# Overo_Carrier.net
KiCad netlist of a schematic drawn in Altium Designer
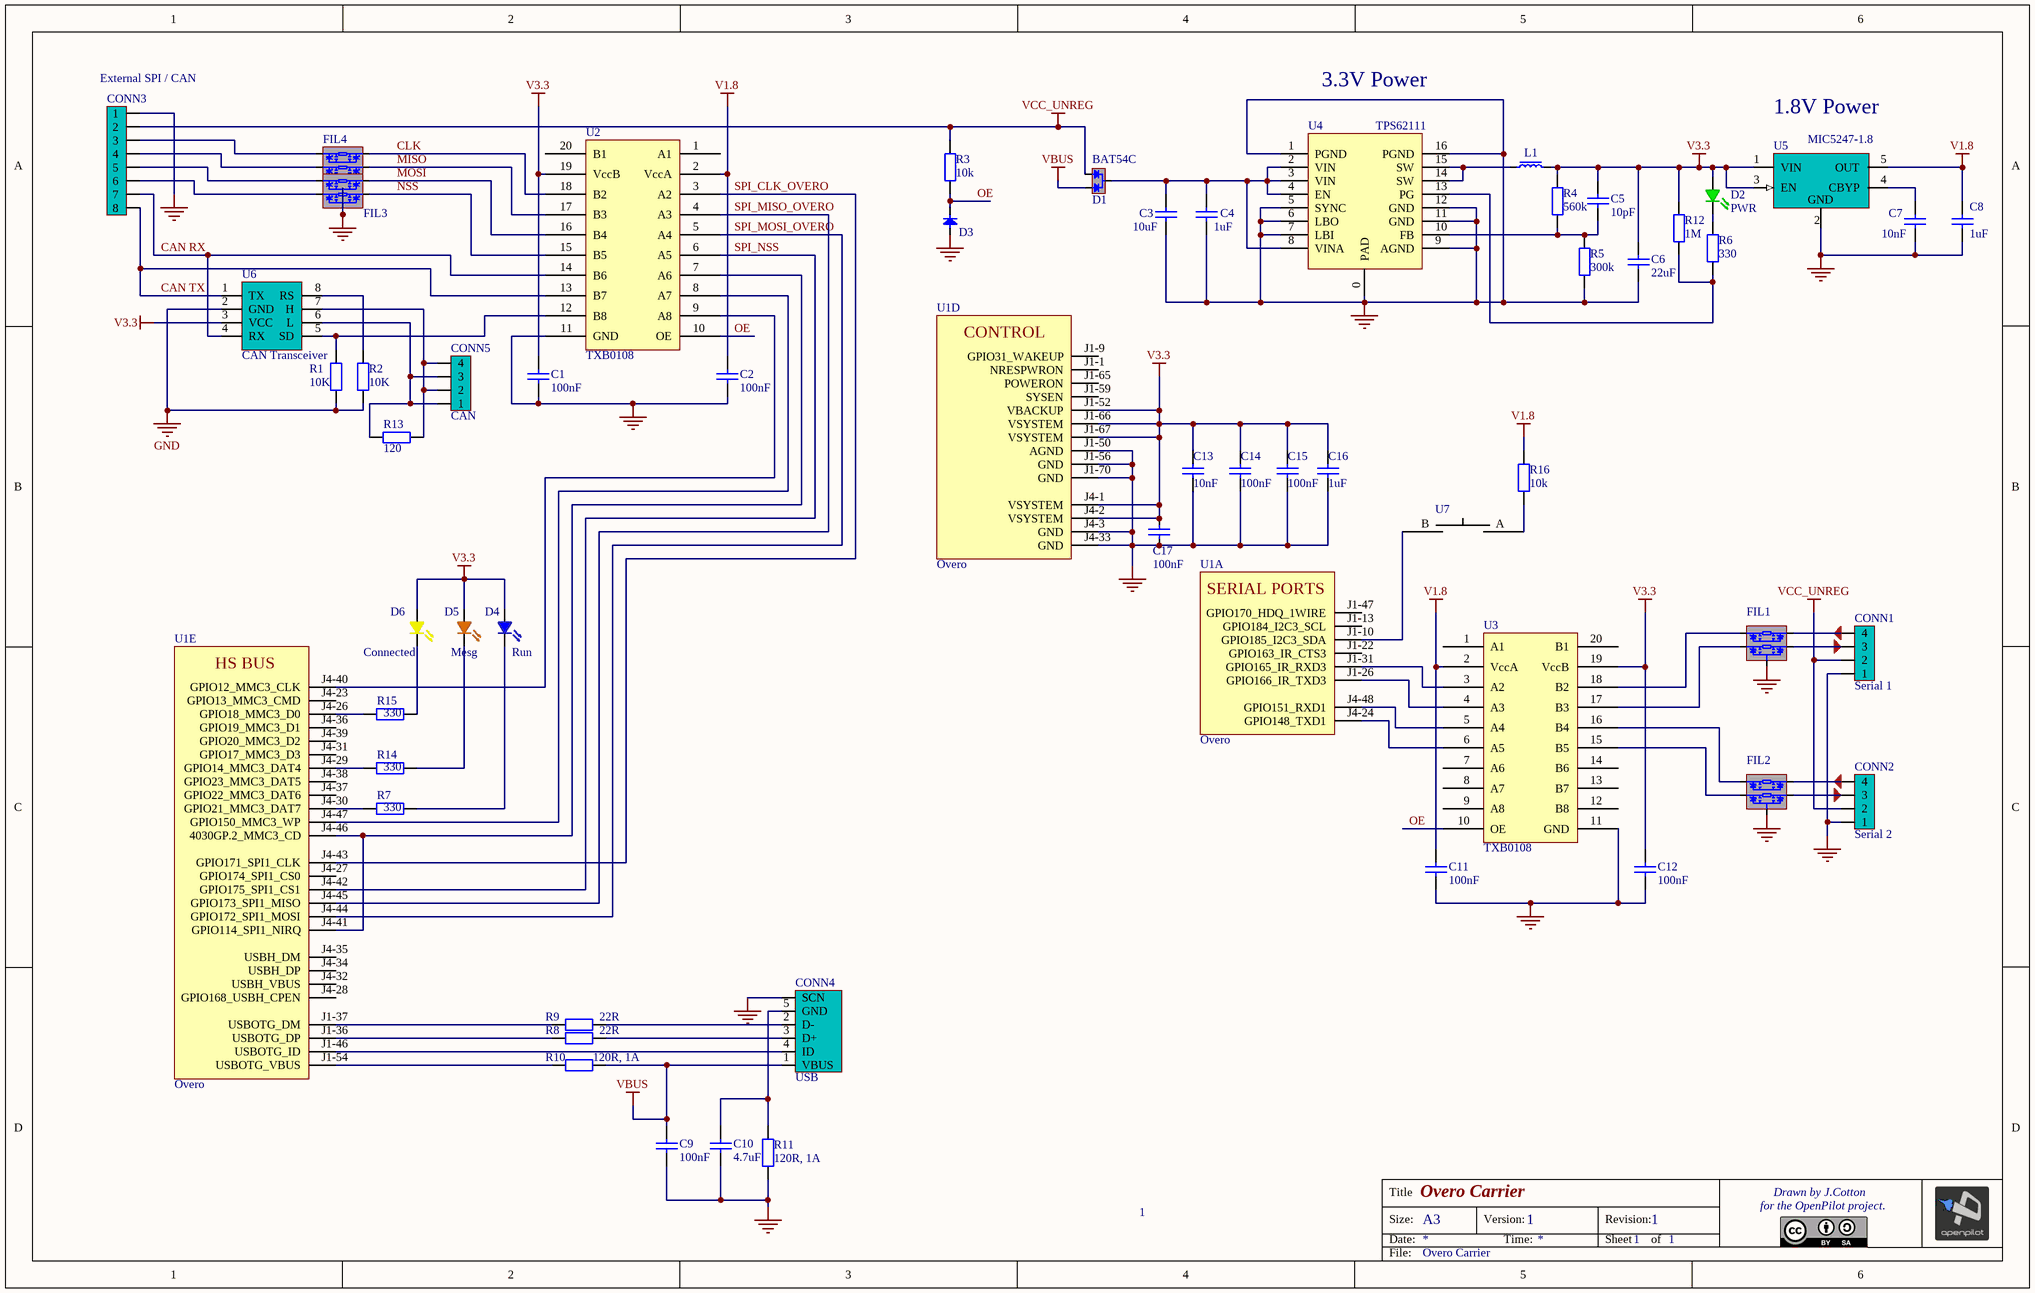
[diagram p0: Overo Carrier.SchDoc]

(export (version "E")
  (design (tool "Eeschema 10.0.6"))
  (components
    (comp (ref "C1")
      (value "100nF")
      (footprint "CAP603N")
      (description "Capacitor SMD")
      (fields (field (name "Comment") "Cap603") (field (name "PUBLISHER") "The OpenPilot Project"))
      (libsource (lib "OpenPilot") (part "Cap603"))
    )
    (comp (ref "C2")
      (value "100nF")
      (footprint "CAP603N")
      (description "Capacitor SMD")
      (fields (field (name "Comment") "Cap603") (field (name "PUBLISHER") "The OpenPilot Project"))
      (libsource (lib "OpenPilot") (part "Cap603"))
    )
    (comp (ref "C3")
      (value "10uF")
      (footprint "CAP805N")
      (description "Capacitor SMD")
      (fields (field (name "Comment") "Cap805") (field (name "PUBLISHER") "The OpenPilot Project"))
      (libsource (lib "OpenPilot") (part "Cap805"))
    )
    (comp (ref "C4")
      (value "1uF")
      (footprint "CAP603L")
      (description "Capacitor SMD")
      (fields (field (name "Comment") "Cap603") (field (name "PUBLISHER") "The OpenPilot Project"))
      (libsource (lib "OpenPilot") (part "Cap603"))
    )
    (comp (ref "C5")
      (value "10pF")
      (footprint "CAP603N")
      (description "Capacitor SMD")
      (fields (field (name "Comment") "Cap603") (field (name "PUBLISHER") "The OpenPilot Project"))
      (libsource (lib "OpenPilot") (part "Cap603"))
    )
    (comp (ref "C6")
      (value "22uF")
      (footprint "CAP805N")
      (description "Capacitor SMD")
      (fields (field (name "Comment") "Cap805") (field (name "PUBLISHER") "The OpenPilot Project"))
      (libsource (lib "OpenPilot") (part "Cap805"))
    )
    (comp (ref "C7")
      (value "10nF")
      (footprint "CAP603N")
      (description "Capacitor SMD")
      (fields (field (name "Comment") "Cap603") (field (name "PUBLISHER") "The OpenPilot Project"))
      (libsource (lib "OpenPilot") (part "Cap603"))
    )
    (comp (ref "C8")
      (value "1uF")
      (footprint "CAP603L")
      (description "Capacitor SMD")
      (fields (field (name "Comment") "Cap603") (field (name "PUBLISHER") "The OpenPilot Project"))
      (libsource (lib "OpenPilot") (part "Cap603"))
    )
    (comp (ref "C9")
      (value "100nF")
      (footprint "CAP603N")
      (description "Capacitor SMD")
      (fields (field (name "Comment") "Cap603") (field (name "PUBLISHER") "The OpenPilot Project"))
      (libsource (lib "OpenPilot") (part "Cap603"))
    )
    (comp (ref "C10")
      (value "4.7uF")
      (footprint "CAP603L")
      (description "Capacitor SMD")
      (fields (field (name "Comment") "Cap603") (field (name "PUBLISHER") "The OpenPilot Project"))
      (libsource (lib "OpenPilot") (part "Cap603"))
    )
    (comp (ref "C11")
      (value "100nF")
      (footprint "CAP603N")
      (description "Capacitor SMD")
      (fields (field (name "Comment") "Cap603") (field (name "PUBLISHER") "The OpenPilot Project"))
      (libsource (lib "OpenPilot") (part "Cap603"))
    )
    (comp (ref "C12")
      (value "100nF")
      (footprint "CAP603N")
      (description "Capacitor SMD")
      (fields (field (name "Comment") "Cap603") (field (name "PUBLISHER") "The OpenPilot Project"))
      (libsource (lib "OpenPilot") (part "Cap603"))
    )
    (comp (ref "C13")
      (value "10nF")
      (footprint "CAP603N")
      (description "Capacitor SMD")
      (fields (field (name "Comment") "Cap603") (field (name "PUBLISHER") "The OpenPilot Project"))
      (libsource (lib "OpenPilot") (part "Cap603"))
    )
    (comp (ref "C14")
      (value "100nF")
      (footprint "CAP603N")
      (description "Capacitor SMD")
      (fields (field (name "Comment") "Cap603") (field (name "PUBLISHER") "The OpenPilot Project"))
      (libsource (lib "OpenPilot") (part "Cap603"))
    )
    (comp (ref "C15")
      (value "100nF")
      (footprint "CAP603N")
      (description "Capacitor SMD")
      (fields (field (name "Comment") "Cap603") (field (name "PUBLISHER") "The OpenPilot Project"))
      (libsource (lib "OpenPilot") (part "Cap603"))
    )
    (comp (ref "C16")
      (value "1uF")
      (footprint "CAP603L")
      (description "Capacitor SMD")
      (fields (field (name "Comment") "Cap603") (field (name "PUBLISHER") "The OpenPilot Project"))
      (libsource (lib "OpenPilot") (part "Cap603"))
    )
    (comp (ref "C17")
      (value "100nF")
      (footprint "CAP603N")
      (description "Capacitor SMD")
      (fields (field (name "Comment") "Cap603") (field (name "PUBLISHER") "The OpenPilot Project"))
      (libsource (lib "") (part "Cap603_1"))
    )
    (comp (ref "CONN1")
      (value "Serial 1")
      (footprint "JST SH 4 Pin Side Entry")
      (description "JST-SH 4-pin Side Entry Socket")
      (fields (field (name "MANUFACTURER") "Generic Components"))
      (libsource (lib "OpenPilot") (part "JST-SH 4-pin Side Entry Socket"))
    )
    (comp (ref "CONN2")
      (value "Serial 2")
      (footprint "JST SH 4 Pin Side Entry")
      (description "JST-SH 4-pin Side Entry Socket")
      (fields (field (name "MANUFACTURER") "Generic Components"))
      (libsource (lib "OpenPilot") (part "JST-SH 4-pin Side Entry Socket"))
    )
    (comp (ref "CONN3")
      (value "External SPI / CAN")
      (footprint "JST SH 8 Pin Side Entry")
      (description "JST-SH 8-pin Side Entry Socket")
      (fields
        (field (name "MANUFACTURER") "Generic Components")
        (field (name "PUBLISHER") "The OpenPilot Project")
      )
      (libsource (lib "OpenPilot") (part "JST-SH 8-pin Side Entry Socket"))
    )
    (comp (ref "CONN4")
      (value "USB")
      (footprint "USB SMD")
      (description "USB Type-B SMT Socket")
      (libsource (lib "OpenPilot") (part "USB_SMT_B"))
    )
    (comp (ref "CONN5")
      (value "CAN")
      (footprint "JST SH 4 Pin Side Entry")
      (description "JST-SH 4-pin Side Entry Socket")
      (fields (field (name "MANUFACTURER") "Generic Components"))
      (libsource (lib "OpenPilot") (part "JST-SH 4-pin Side Entry Socket"))
    )
    (comp (ref "D1")
      (value "BAT54C")
      (footprint "SOT23-3N")
      (description "Dual Diode Command Cathode")
      (fields
        (field (name "MANUFACTURER") "STMicroelectronics")
        (field (name "MANUFACTURER PART NUMBER") "BAT54CFILM")
      )
      (libsource (lib "OpenPilot") (part "BAT54C"))
    )
    (comp (ref "D2")
      (value "PWR")
      (footprint "LED603N")
      (description "Green 603 LED")
      (libsource (lib "OpenPilot") (part "LED 603 Gr"))
    )
    (comp (ref "D3")
      (value "Diode Zen 3.3V 0603")
      (footprint "IND603N")
      (description "Diode Zener 3.3V 150MW 0603")
      (libsource (lib "OpenPilot") (part "Diode Zener 3.3V 150MW 0603"))
    )
    (comp (ref "D4")
      (value "Run")
      (footprint "LED603N")
      (description "Blue 603 LED")
      (libsource (lib "OpenPilot") (part "LED 603 Bl"))
    )
    (comp (ref "D5")
      (value "Mesg")
      (footprint "LED603N")
      (description "Orange 603 LED")
      (fields (field (name "PUBLISHER") "The OpenPilot Project"))
      (libsource (lib "OpenPilot") (part "LED 603 Or"))
    )
    (comp (ref "D6")
      (value "Connected")
      (footprint "LED603N")
      (description "Yellow 603 LED")
      (fields (field (name "PUBLISHER") "The OpenPilot Project"))
      (libsource (lib "OpenPilot") (part "LED 603 Yellow"))
    )
    (comp (ref "FIL1")
      (value "IP4256CZ5-W,115")
      (footprint "SOT-665")
      (description "IP4256CZ5-W,115 2 channel, 100R, 30pF, RF ESD Filter")
      (fields
        (field (name "MANUFACTURER") "Generic Components")
        (field (name "PUBLISHER") "The OpenPilot Project")
      )
      (libsource (lib "OpenPilot") (part "RF Filter 100R 30pF"))
    )
    (comp (ref "FIL2")
      (value "IP4256CZ5-W,115")
      (footprint "SOT-665")
      (description "IP4256CZ5-W,115 2 channel, 100R, 30pF, RF ESD Filter")
      (fields
        (field (name "MANUFACTURER") "Generic Components")
        (field (name "PUBLISHER") "The OpenPilot Project")
      )
      (libsource (lib "OpenPilot") (part "RF Filter 100R 30pF"))
    )
    (comp (ref "FIL3")
      (value "IP4256CZ5-W,115")
      (footprint "SOT-665")
      (description "IP4256CZ5-W,115 2 channel, 100R, 30pF, RF ESD Filter")
      (fields
        (field (name "MANUFACTURER") "Generic Components")
        (field (name "PUBLISHER") "The OpenPilot Project")
      )
      (libsource (lib "") (part "RF Filter 100R 30pF_1"))
    )
    (comp (ref "FIL4")
      (value "IP4256CZ5-W,115")
      (footprint "SOT-665")
      (description "IP4256CZ5-W,115 2 channel, 100R, 30pF, RF ESD Filter")
      (fields
        (field (name "MANUFACTURER") "Generic Components")
        (field (name "PUBLISHER") "The OpenPilot Project")
      )
      (libsource (lib "") (part "RF Filter 100R 30pF_1"))
    )
    (comp (ref "L1")
      (value "FB 550mA 6.8µH 0805")
      (footprint "IND805L")
      (description "Ferrite Bead 550mA 6.8µH")
      (fields
        (field (name "MANUFACTURER") "Generic Components")
        (field (name "PUBLISHER") "The OpenPilot Project")
      )
      (libsource (lib "OpenPilot") (part "Ferrite Bead 550mA 6.8µH 0805"))
    )
    (comp (ref "R1")
      (value "10K")
      (footprint "RES603N")
      (description "Resistor SMD")
      (fields (field (name "Comment") "Res603") (field (name "PUBLISHER") "The OpenPilot Project"))
      (libsource (lib "OpenPilot") (part "Res603"))
    )
    (comp (ref "R2")
      (value "10K")
      (footprint "RES603N")
      (description "Resistor SMD")
      (fields (field (name "Comment") "Res603") (field (name "PUBLISHER") "The OpenPilot Project"))
      (libsource (lib "OpenPilot") (part "Res603"))
    )
    (comp (ref "R3")
      (value "10k")
      (footprint "RES603N")
      (description "Resistor SMD")
      (fields (field (name "Comment") "Res603") (field (name "PUBLISHER") "The OpenPilot Project"))
      (libsource (lib "") (part "Res603_1"))
    )
    (comp (ref "R4")
      (value "560k")
      (footprint "RES603N")
      (description "Resistor SMD")
      (fields (field (name "Comment") "Res603") (field (name "PUBLISHER") "The OpenPilot Project"))
      (libsource (lib "OpenPilot") (part "Res603"))
    )
    (comp (ref "R5")
      (value "300k")
      (footprint "RES603N")
      (description "Resistor SMD")
      (fields (field (name "Comment") "Res603") (field (name "PUBLISHER") "The OpenPilot Project"))
      (libsource (lib "OpenPilot") (part "Res603"))
    )
    (comp (ref "R6")
      (value "330")
      (footprint "RES603N")
      (description "Resistor SMD")
      (fields (field (name "Comment") "Res603") (field (name "PUBLISHER") "The OpenPilot Project"))
      (libsource (lib "OpenPilot") (part "Res603"))
    )
    (comp (ref "R7")
      (value "330")
      (footprint "RES603N")
      (description "Resistor SMD")
      (fields (field (name "Comment") "Res603") (field (name "PUBLISHER") "The OpenPilot Project"))
      (libsource (lib "") (part "Res603_3"))
    )
    (comp (ref "R8")
      (value "22R")
      (footprint "RES603N")
      (description "Resistor SMD")
      (fields (field (name "Comment") "Res603") (field (name "PUBLISHER") "The OpenPilot Project"))
      (libsource (lib "") (part "Res603_2"))
    )
    (comp (ref "R9")
      (value "22R")
      (footprint "RES603N")
      (description "Resistor SMD")
      (fields (field (name "Comment") "Res603") (field (name "PUBLISHER") "The OpenPilot Project"))
      (libsource (lib "") (part "Res603_2"))
    )
    (comp (ref "R10")
      (value "120R, 1A")
      (footprint "RES805L")
      (description "Resistor SMD")
      (fields (field (name "Comment") "Res805") (field (name "PUBLISHER") "The OpenPilot Project"))
      (libsource (lib "OpenPilot") (part "Res805"))
    )
    (comp (ref "R11")
      (value "120R, 1A")
      (footprint "RES805L")
      (description "Resistor SMD")
      (fields (field (name "Comment") "Res805") (field (name "PUBLISHER") "The OpenPilot Project"))
      (libsource (lib "") (part "Res805_1"))
    )
    (comp (ref "R12")
      (value "1M")
      (footprint "RES603N")
      (description "Resistor SMD")
      (fields (field (name "Comment") "Res603") (field (name "PUBLISHER") "The OpenPilot Project"))
      (libsource (lib "") (part "Res603_1"))
    )
    (comp (ref "R13")
      (value "120")
      (footprint "RES603N")
      (description "Resistor SMD")
      (fields (field (name "Comment") "Res603") (field (name "PUBLISHER") "The OpenPilot Project"))
      (libsource (lib "") (part "Res603_3"))
    )
    (comp (ref "R14")
      (value "330")
      (footprint "RES603N")
      (description "Resistor SMD")
      (fields (field (name "Comment") "Res603") (field (name "PUBLISHER") "The OpenPilot Project"))
      (libsource (lib "") (part "Res603_2"))
    )
    (comp (ref "R15")
      (value "330")
      (footprint "RES603N")
      (description "Resistor SMD")
      (fields (field (name "Comment") "Res603") (field (name "PUBLISHER") "The OpenPilot Project"))
      (libsource (lib "") (part "Res603_2"))
    )
    (comp (ref "R16")
      (value "10k")
      (footprint "RES603N")
      (description "Resistor SMD")
      (fields (field (name "Comment") "Res603") (field (name "PUBLISHER") "The OpenPilot Project"))
      (libsource (lib "") (part "Res603_1"))
    )
    (comp (ref "U1")
      (value "Overo")
      (footprint "OVERO")
      (description "Gumstix Overo COM")
      (libsource (lib "Gumstix") (part "Overo"))
    )
    (comp (ref "U2")
      (value "TXB0108")
      (footprint "SOP65P640X162-20N")
      (description "Bidirection level shifter")
      (libsource (lib "OpenPilot") (part "TXB0108PW"))
    )
    (comp (ref "U3")
      (value "TXB0108")
      (footprint "SOP65P640X162-20N")
      (description "Bidirection level shifter")
      (libsource (lib "") (part "TXB0108PW_1"))
    )
    (comp (ref "U4")
      (value "TPS62111")
      (footprint "QFN65P400X400X100-16N")
      (description "Step-Down Buck 3.3V")
      (libsource (lib "OpenPilot") (part "TPS62111"))
    )
    (comp (ref "U5")
      (value "MIC5247-1.8")
      (footprint "SOT23-5L")
      (description "1.8V 150mA LDO Regulator A Grade")
      (fields (field (name "PUBLISHER") "The OpenPilot Project"))
      (libsource (lib "OpenPilot") (part "MIC5247-1.8"))
    )
    (comp (ref "U6")
      (value "CAN Transceiver")
      (footprint "SOT23-8")
      (description "CAN Transceiver MAX3051")
      (fields (field (name "PUBLISHER") "The OpenPilot Project"))
      (libsource (lib "OpenPilot") (part "CAN MAX3051"))
    )
    (comp (ref "U7")
      (value "Switch push Button")
      (footprint "EVQ-Q2K03W")
      (description "Switch")
      (libsource (lib "OpenPilot") (part "Push Switch"))
    )
  )
  (nets
    (net (code "1") (name "/CAN RX") (class "Default")
      (node (ref "CONN3") (pin "7") (pinfunction "7_7") (pintype "passive"))
      (node (ref "U2") (pin "14") (pinfunction "B6_14") (pintype "passive"))
      (node (ref "U6") (pin "4") (pinfunction "RX_4") (pintype "passive"))
    )
    (net (code "2") (name "/CAN TX") (class "Default")
      (node (ref "CONN3") (pin "8") (pinfunction "8_8") (pintype "passive"))
      (node (ref "U2") (pin "13") (pinfunction "B7_13") (pintype "passive"))
      (node (ref "U6") (pin "1") (pinfunction "TX_1") (pintype "passive"))
    )
    (net (code "3") (name "/CLK") (class "Default")
      (node (ref "FIL4") (pin "3") (pinfunction "3_3") (pintype "passive"))
      (node (ref "U2") (pin "18") (pinfunction "B2_18") (pintype "passive"))
    )
    (net (code "4") (name "/MISO") (class "Default")
      (node (ref "FIL4") (pin "1") (pinfunction "1_1") (pintype "passive"))
      (node (ref "U2") (pin "17") (pinfunction "B3_17") (pintype "passive"))
    )
    (net (code "5") (name "/MOSI") (class "Default")
      (node (ref "FIL3") (pin "3") (pinfunction "3_3") (pintype "passive"))
      (node (ref "U2") (pin "16") (pinfunction "B4_16") (pintype "passive"))
    )
    (net (code "6") (name "/NSS") (class "Default")
      (node (ref "FIL3") (pin "1") (pinfunction "1_1") (pintype "passive"))
      (node (ref "U2") (pin "15") (pinfunction "B5_15") (pintype "passive"))
    )
    (net (code "7") (name "/OE") (class "Default")
      (node (ref "D3") (pin "1") (pinfunction "K_1") (pintype "passive"))
      (node (ref "R3") (pin "2") (pinfunction "2_2") (pintype "passive"))
      (node (ref "U2") (pin "10") (pinfunction "OE_10") (pintype "passive"))
      (node (ref "U3") (pin "10") (pinfunction "OE_10") (pintype "passive"))
    )
    (net (code "8") (name "/SPI_CLK_OVERO") (class "Default")
      (node (ref "U1") (pin "J4-43") (pinfunction "GPIO171_SPI1_CLK_J4-43") (pintype "passive"))
      (node (ref "U2") (pin "3") (pinfunction "A2_3") (pintype "passive"))
    )
    (net (code "9") (name "/SPI_MISO_OVERO") (class "Default")
      (node (ref "U1") (pin "J4-45") (pinfunction "GPIO173_SPI1_MISO_J4-45") (pintype "passive"))
      (node (ref "U2") (pin "4") (pinfunction "A3_4") (pintype "passive"))
    )
    (net (code "10") (name "/SPI_MOSI_OVERO") (class "Default")
      (node (ref "U1") (pin "J4-44") (pinfunction "GPIO172_SPI1_MOSI_J4-44") (pintype "passive"))
      (node (ref "U2") (pin "5") (pinfunction "A4_5") (pintype "passive"))
    )
    (net (code "11") (name "/SPI_NSS") (class "Default")
      (node (ref "U1") (pin "J4-42") (pinfunction "GPIO175_SPI1_CS1_J4-42") (pintype "passive"))
      (node (ref "U2") (pin "6") (pinfunction "A5_6") (pintype "passive"))
    )
    (net (code "12") (name "GND") (class "Default")
      (node (ref "C1") (pin "1") (pinfunction "1_1") (pintype "passive"))
      (node (ref "C10") (pin "1") (pinfunction "1_1") (pintype "passive"))
      (node (ref "C11") (pin "1") (pinfunction "1_1") (pintype "passive"))
      (node (ref "C12") (pin "1") (pinfunction "1_1") (pintype "passive"))
      (node (ref "C13") (pin "1") (pinfunction "1_1") (pintype "passive"))
      (node (ref "C14") (pin "1") (pinfunction "1_1") (pintype "passive"))
      (node (ref "C15") (pin "2") (pinfunction "2_2") (pintype "passive"))
      (node (ref "C16") (pin "1") (pinfunction "1_1") (pintype "passive"))
      (node (ref "C17") (pin "1") (pinfunction "1_1") (pintype "passive"))
      (node (ref "C2") (pin "1") (pinfunction "1_1") (pintype "passive"))
      (node (ref "C3") (pin "1") (pinfunction "1_1") (pintype "passive"))
      (node (ref "C4") (pin "1") (pinfunction "1_1") (pintype "passive"))
      (node (ref "C6") (pin "1") (pinfunction "1_1") (pintype "passive"))
      (node (ref "C7") (pin "1") (pinfunction "1_1") (pintype "passive"))
      (node (ref "C8") (pin "1") (pinfunction "1_1") (pintype "passive"))
      (node (ref "C9") (pin "1") (pinfunction "1_1") (pintype "passive"))
      (node (ref "CONN1") (pin "1") (pinfunction "1_1") (pintype "passive"))
      (node (ref "CONN2") (pin "1") (pinfunction "1_1") (pintype "passive"))
      (node (ref "CONN3") (pin "1") (pinfunction "1_1") (pintype "passive"))
      (node (ref "CONN4") (pin "0") (pinfunction "SCN_0") (pintype "passive"))
      (node (ref "D3") (pin "2") (pinfunction "A_2") (pintype "passive"))
      (node (ref "FIL1") (pin "2") (pinfunction "PAD_2") (pintype "passive"))
      (node (ref "FIL2") (pin "2") (pinfunction "PAD_2") (pintype "passive"))
      (node (ref "FIL3") (pin "2") (pinfunction "PAD_2") (pintype "passive"))
      (node (ref "FIL4") (pin "2") (pinfunction "PAD_2") (pintype "passive"))
      (node (ref "R1") (pin "1") (pinfunction "1_1") (pintype "passive"))
      (node (ref "R11") (pin "2") (pinfunction "2_2") (pintype "passive"))
      (node (ref "R2") (pin "1") (pinfunction "1_1") (pintype "passive"))
      (node (ref "R5") (pin "1") (pinfunction "1_1") (pintype "passive"))
      (node (ref "U1") (pin "J1-50") (pinfunction "AGND_J1-50") (pintype "passive"))
      (node (ref "U1") (pin "J1-56") (pinfunction "GND_J1-56") (pintype "passive"))
      (node (ref "U1") (pin "J1-70") (pinfunction "GND_J1-70") (pintype "passive"))
      (node (ref "U1") (pin "J4-3") (pinfunction "GND_J4-3") (pintype "passive"))
      (node (ref "U1") (pin "J4-33") (pinfunction "GND_J4-33") (pintype "passive"))
      (node (ref "U2") (pin "11") (pinfunction "GND_11") (pintype "passive"))
      (node (ref "U3") (pin "11") (pinfunction "GND_11") (pintype "passive"))
      (node (ref "U4") (pin "0") (pinfunction "PAD_0") (pintype "passive"))
      (node (ref "U4") (pin "1") (pinfunction "PGND_1") (pintype "power_in"))
      (node (ref "U4") (pin "11") (pinfunction "GND_11") (pintype "power_in"))
      (node (ref "U4") (pin "12") (pinfunction "GND_12") (pintype "power_in"))
      (node (ref "U4") (pin "16") (pinfunction "PGND_16") (pintype "power_in"))
      (node (ref "U4") (pin "5") (pinfunction "SYNC_5") (pintype "passive"))
      (node (ref "U4") (pin "6") (pinfunction "LBO_6") (pintype "passive"))
      (node (ref "U4") (pin "7") (pinfunction "LBI_7") (pintype "passive"))
      (node (ref "U4") (pin "9") (pinfunction "AGND_9") (pintype "passive"))
      (node (ref "U5") (pin "2") (pinfunction "GND_2") (pintype "power_in"))
      (node (ref "U6") (pin "2") (pinfunction "GND_2") (pintype "passive"))
    )
    (net (code "13") (name "Net-(CONN1-Pad3)") (class "Default")
      (node (ref "CONN1") (pin "3") (pinfunction "3_3") (pintype "passive"))
      (node (ref "FIL1") (pin "4") (pinfunction "4_4") (pintype "passive"))
    )
    (net (code "14") (name "Net-(CONN1-Pad4)") (class "Default")
      (node (ref "CONN1") (pin "4") (pinfunction "4_4") (pintype "passive"))
      (node (ref "FIL1") (pin "5") (pinfunction "5_5") (pintype "passive"))
    )
    (net (code "15") (name "Net-(CONN2-Pad3)") (class "Default")
      (node (ref "CONN2") (pin "3") (pinfunction "3_3") (pintype "passive"))
      (node (ref "FIL2") (pin "4") (pinfunction "4_4") (pintype "passive"))
    )
    (net (code "16") (name "Net-(CONN2-Pad4)") (class "Default")
      (node (ref "CONN2") (pin "4") (pinfunction "4_4") (pintype "passive"))
      (node (ref "FIL2") (pin "5") (pinfunction "5_5") (pintype "passive"))
    )
    (net (code "17") (name "Net-(CONN3-Pad3)") (class "Default")
      (node (ref "CONN3") (pin "3") (pinfunction "3_3") (pintype "passive"))
      (node (ref "FIL4") (pin "4") (pinfunction "4_4") (pintype "passive"))
    )
    (net (code "18") (name "Net-(CONN3-Pad4)") (class "Default")
      (node (ref "CONN3") (pin "4") (pinfunction "4_4") (pintype "passive"))
      (node (ref "FIL4") (pin "5") (pinfunction "5_5") (pintype "passive"))
    )
    (net (code "19") (name "Net-(CONN3-Pad5)") (class "Default")
      (node (ref "CONN3") (pin "5") (pinfunction "5_5") (pintype "passive"))
      (node (ref "FIL3") (pin "4") (pinfunction "4_4") (pintype "passive"))
    )
    (net (code "20") (name "Net-(CONN3-Pad6)") (class "Default")
      (node (ref "CONN3") (pin "6") (pinfunction "6_6") (pintype "passive"))
      (node (ref "FIL3") (pin "5") (pinfunction "5_5") (pintype "passive"))
    )
    (net (code "21") (name "Net-(CONN4-D+)") (class "Default")
      (node (ref "CONN4") (pin "3") (pinfunction "D+_3") (pintype "passive"))
      (node (ref "R8") (pin "1") (pinfunction "1_1") (pintype "passive"))
    )
    (net (code "22") (name "Net-(CONN4-D-)") (class "Default")
      (node (ref "CONN4") (pin "2") (pinfunction "D-_2") (pintype "passive"))
      (node (ref "R9") (pin "1") (pinfunction "1_1") (pintype "passive"))
    )
    (net (code "23") (name "Net-(CONN4-GND)") (class "Default")
      (node (ref "C10") (pin "2") (pinfunction "2_2") (pintype "passive"))
      (node (ref "CONN4") (pin "5") (pinfunction "GND_5") (pintype "passive"))
      (node (ref "R11") (pin "1") (pinfunction "1_1") (pintype "passive"))
    )
    (net (code "24") (name "Net-(CONN4-ID)") (class "Default")
      (node (ref "CONN4") (pin "4") (pinfunction "ID_4") (pintype "passive"))
      (node (ref "U1") (pin "J1-46") (pinfunction "USBOTG_ID_J1-46") (pintype "passive"))
    )
    (net (code "25") (name "Net-(D1-COM)") (class "Default")
      (node (ref "C3") (pin "2") (pinfunction "2_2") (pintype "passive"))
      (node (ref "C4") (pin "2") (pinfunction "2_2") (pintype "passive"))
      (node (ref "D1") (pin "3") (pinfunction "COM_3") (pintype "passive"))
      (node (ref "U4") (pin "2") (pinfunction "VIN_2") (pintype "power_in"))
      (node (ref "U4") (pin "3") (pinfunction "VIN_3") (pintype "power_in"))
      (node (ref "U4") (pin "4") (pinfunction "EN_4") (pintype "passive"))
      (node (ref "U4") (pin "8") (pinfunction "VINA_8") (pintype "passive"))
    )
    (net (code "26") (name "Net-(D2-K)") (class "Default")
      (node (ref "D2") (pin "1") (pinfunction "K_1") (pintype "passive"))
      (node (ref "R6") (pin "2") (pinfunction "2_2") (pintype "passive"))
    )
    (net (code "27") (name "Net-(D4-K)") (class "Default")
      (node (ref "D4") (pin "1") (pinfunction "K_1") (pintype "passive"))
      (node (ref "R7") (pin "2") (pinfunction "2_2") (pintype "passive"))
    )
    (net (code "28") (name "Net-(D5-K)") (class "Default")
      (node (ref "D5") (pin "1") (pinfunction "K_1") (pintype "passive"))
      (node (ref "R14") (pin "1") (pinfunction "1_1") (pintype "passive"))
    )
    (net (code "29") (name "Net-(D6-K)") (class "Default")
      (node (ref "D6") (pin "1") (pinfunction "K_1") (pintype "passive"))
      (node (ref "R15") (pin "1") (pinfunction "1_1") (pintype "passive"))
    )
    (net (code "30") (name "Net-(L1-Pad1)") (class "Default")
      (node (ref "L1") (pin "1") (pinfunction "1_1") (pintype "passive"))
      (node (ref "U4") (pin "14") (pinfunction "SW_14") (pintype "passive"))
      (node (ref "U4") (pin "15") (pinfunction "SW_15") (pintype "passive"))
    )
    (net (code "31") (name "Net-(R16-Pad2)") (class "Default")
      (node (ref "R16") (pin "2") (pinfunction "2_2") (pintype "passive"))
      (node (ref "U7") (pin "A") (pinfunction "A_A") (pintype "power_in"))
    )
    (net (code "32") (name "Net-(U1A-GPIO148_TXD1)") (class "Default")
      (node (ref "U1") (pin "J4-24") (pinfunction "GPIO148_TXD1_J4-24") (pintype "passive"))
      (node (ref "U3") (pin "6") (pinfunction "A5_6") (pintype "passive"))
    )
    (net (code "33") (name "Net-(U1A-GPIO151_RXD1)") (class "Default")
      (node (ref "U1") (pin "J4-48") (pinfunction "GPIO151_RXD1_J4-48") (pintype "passive"))
      (node (ref "U3") (pin "5") (pinfunction "A4_5") (pintype "passive"))
    )
    (net (code "34") (name "Net-(U1A-GPIO165_IR_RXD3)") (class "Default")
      (node (ref "U1") (pin "J1-31") (pinfunction "GPIO165_IR_RXD3_J1-31") (pintype "passive"))
      (node (ref "U3") (pin "3") (pinfunction "A2_3") (pintype "passive"))
    )
    (net (code "35") (name "Net-(U1A-GPIO166_IR_TXD3)") (class "Default")
      (node (ref "U1") (pin "J1-26") (pinfunction "GPIO166_IR_TXD3_J1-26") (pintype "passive"))
      (node (ref "U3") (pin "4") (pinfunction "A3_4") (pintype "passive"))
    )
    (net (code "36") (name "Net-(U1A-GPIO185_I2C3_SDA)") (class "Default")
      (node (ref "U1") (pin "J1-10") (pinfunction "GPIO185_I2C3_SDA_J1-10") (pintype "passive"))
      (node (ref "U7") (pin "B") (pinfunction "B_B") (pintype "power_in"))
    )
    (net (code "37") (name "Net-(U1E-4030GP.2_MMC3_CD)") (class "Default")
      (node (ref "U1") (pin "J4-41") (pinfunction "GPIO114_SPI1_NIRQ_J4-41") (pintype "passive"))
      (node (ref "U1") (pin "J4-46") (pinfunction "4030GP.2_MMC3_CD_J4-46") (pintype "passive"))
      (node (ref "U2") (pin "7") (pinfunction "A6_7") (pintype "passive"))
    )
    (net (code "38") (name "Net-(U1E-GPIO12_MMC3_CLK)") (class "Default")
      (node (ref "U1") (pin "J4-40") (pinfunction "GPIO12_MMC3_CLK_J4-40") (pintype "passive"))
      (node (ref "U2") (pin "9") (pinfunction "A8_9") (pintype "passive"))
    )
    (net (code "39") (name "Net-(U1E-GPIO14_MMC3_DAT4)") (class "Default")
      (node (ref "R14") (pin "2") (pinfunction "2_2") (pintype "passive"))
      (node (ref "U1") (pin "J4-29") (pinfunction "GPIO14_MMC3_DAT4_J4-29") (pintype "passive"))
    )
    (net (code "40") (name "Net-(U1E-GPIO18_MMC3_D0)") (class "Default")
      (node (ref "R15") (pin "2") (pinfunction "2_2") (pintype "passive"))
      (node (ref "U1") (pin "J4-26") (pinfunction "GPIO18_MMC3_D0_J4-26") (pintype "passive"))
    )
    (net (code "41") (name "Net-(U1E-GPIO21_MMC3_DAT7)") (class "Default")
      (node (ref "R7") (pin "1") (pinfunction "1_1") (pintype "passive"))
      (node (ref "U1") (pin "J4-30") (pinfunction "GPIO21_MMC3_DAT7_J4-30") (pintype "passive"))
    )
    (net (code "42") (name "Net-(U1E-GPIO150_MMC3_WP)") (class "Default")
      (node (ref "U1") (pin "J4-47") (pinfunction "GPIO150_MMC3_WP_J4-47") (pintype "passive"))
      (node (ref "U2") (pin "8") (pinfunction "A7_8") (pintype "passive"))
    )
    (net (code "43") (name "Net-(U1E-USBOTG_DM)") (class "Default")
      (node (ref "R9") (pin "2") (pinfunction "2_2") (pintype "passive"))
      (node (ref "U1") (pin "J1-37") (pinfunction "USBOTG_DM_J1-37") (pintype "passive"))
    )
    (net (code "44") (name "Net-(U1E-USBOTG_DP)") (class "Default")
      (node (ref "R8") (pin "2") (pinfunction "2_2") (pintype "passive"))
      (node (ref "U1") (pin "J1-36") (pinfunction "USBOTG_DP_J1-36") (pintype "passive"))
    )
    (net (code "45") (name "Net-(U1E-USBOTG_VBUS)") (class "Default")
      (node (ref "R10") (pin "2") (pinfunction "2_2") (pintype "passive"))
      (node (ref "U1") (pin "J1-54") (pinfunction "USBOTG_VBUS_J1-54") (pintype "passive"))
    )
    (net (code "46") (name "Net-(U2-B8)") (class "Default")
      (node (ref "R1") (pin "2") (pinfunction "2_2") (pintype "passive"))
      (node (ref "U2") (pin "12") (pinfunction "B8_12") (pintype "passive"))
      (node (ref "U6") (pin "5") (pinfunction "SD_5") (pintype "passive"))
    )
    (net (code "47") (name "Net-(U3-B2)") (class "Default")
      (node (ref "FIL1") (pin "1") (pinfunction "1_1") (pintype "passive"))
      (node (ref "U3") (pin "18") (pinfunction "B2_18") (pintype "passive"))
    )
    (net (code "48") (name "Net-(U3-B3)") (class "Default")
      (node (ref "FIL1") (pin "3") (pinfunction "3_3") (pintype "passive"))
      (node (ref "U3") (pin "17") (pinfunction "B3_17") (pintype "passive"))
    )
    (net (code "49") (name "Net-(U3-B4)") (class "Default")
      (node (ref "FIL2") (pin "1") (pinfunction "1_1") (pintype "passive"))
      (node (ref "U3") (pin "16") (pinfunction "B4_16") (pintype "passive"))
    )
    (net (code "50") (name "Net-(U3-B5)") (class "Default")
      (node (ref "FIL2") (pin "3") (pinfunction "3_3") (pintype "passive"))
      (node (ref "U3") (pin "15") (pinfunction "B5_15") (pintype "passive"))
    )
    (net (code "51") (name "Net-(U4-FB)") (class "Default")
      (node (ref "C5") (pin "1") (pinfunction "1_1") (pintype "passive"))
      (node (ref "R4") (pin "1") (pinfunction "1_1") (pintype "passive"))
      (node (ref "R5") (pin "2") (pinfunction "2_2") (pintype "passive"))
      (node (ref "U4") (pin "10") (pinfunction "FB_10") (pintype "passive"))
    )
    (net (code "52") (name "Net-(U4-PG)") (class "Default")
      (node (ref "R12") (pin "2") (pinfunction "2_2") (pintype "passive"))
      (node (ref "R6") (pin "1") (pinfunction "1_1") (pintype "passive"))
      (node (ref "U4") (pin "13") (pinfunction "PG_13") (pintype "passive"))
    )
    (net (code "53") (name "Net-(U5-CBYP)") (class "Default")
      (node (ref "C7") (pin "2") (pinfunction "2_2") (pintype "passive"))
      (node (ref "U5") (pin "4") (pinfunction "CBYP_4") (pintype "passive"))
    )
    (net (code "54") (name "Net-(U6-H)") (class "Default")
      (node (ref "CONN5") (pin "2") (pinfunction "2_2") (pintype "passive"))
      (node (ref "CONN5") (pin "4") (pinfunction "4_4") (pintype "passive"))
      (node (ref "R13") (pin "2") (pinfunction "2_2") (pintype "passive"))
      (node (ref "U6") (pin "7") (pinfunction "H_7") (pintype "passive"))
    )
    (net (code "55") (name "Net-(U6-L)") (class "Default")
      (node (ref "CONN5") (pin "1") (pinfunction "1_1") (pintype "passive"))
      (node (ref "CONN5") (pin "3") (pinfunction "3_3") (pintype "passive"))
      (node (ref "R13") (pin "1") (pinfunction "1_1") (pintype "passive"))
      (node (ref "U6") (pin "6") (pinfunction "L_6") (pintype "passive"))
    )
    (net (code "56") (name "Net-(U6-RS)") (class "Default")
      (node (ref "R2") (pin "2") (pinfunction "2_2") (pintype "passive"))
      (node (ref "U6") (pin "8") (pinfunction "RS_8") (pintype "passive"))
    )
    (net (code "57") (name "V1.8") (class "Default")
      (node (ref "C11") (pin "2") (pinfunction "2_2") (pintype "passive"))
      (node (ref "C2") (pin "2") (pinfunction "2_2") (pintype "passive"))
      (node (ref "C8") (pin "2") (pinfunction "2_2") (pintype "passive"))
      (node (ref "R16") (pin "1") (pinfunction "1_1") (pintype "passive"))
      (node (ref "U2") (pin "2") (pinfunction "VccA_2") (pintype "passive"))
      (node (ref "U3") (pin "2") (pinfunction "VccA_2") (pintype "passive"))
      (node (ref "U5") (pin "5") (pinfunction "OUT_5") (pintype "power_in"))
    )
    (net (code "58") (name "V3.3") (class "Default")
      (node (ref "C1") (pin "2") (pinfunction "2_2") (pintype "passive"))
      (node (ref "C12") (pin "2") (pinfunction "2_2") (pintype "passive"))
      (node (ref "C13") (pin "2") (pinfunction "2_2") (pintype "passive"))
      (node (ref "C14") (pin "2") (pinfunction "2_2") (pintype "passive"))
      (node (ref "C15") (pin "1") (pinfunction "1_1") (pintype "passive"))
      (node (ref "C16") (pin "2") (pinfunction "2_2") (pintype "passive"))
      (node (ref "C17") (pin "2") (pinfunction "2_2") (pintype "passive"))
      (node (ref "C5") (pin "2") (pinfunction "2_2") (pintype "passive"))
      (node (ref "C6") (pin "2") (pinfunction "2_2") (pintype "passive"))
      (node (ref "D2") (pin "2") (pinfunction "A_2") (pintype "passive"))
      (node (ref "D4") (pin "2") (pinfunction "A_2") (pintype "passive"))
      (node (ref "D5") (pin "2") (pinfunction "A_2") (pintype "passive"))
      (node (ref "D6") (pin "2") (pinfunction "A_2") (pintype "passive"))
      (node (ref "L1") (pin "2") (pinfunction "2_2") (pintype "passive"))
      (node (ref "R12") (pin "1") (pinfunction "1_1") (pintype "passive"))
      (node (ref "R4") (pin "2") (pinfunction "2_2") (pintype "passive"))
      (node (ref "U1") (pin "J1-52") (pinfunction "VBACKUP_J1-52") (pintype "passive"))
      (node (ref "U1") (pin "J1-66") (pinfunction "VSYSTEM_J1-66") (pintype "passive"))
      (node (ref "U1") (pin "J1-67") (pinfunction "VSYSTEM_J1-67") (pintype "passive"))
      (node (ref "U1") (pin "J4-1") (pinfunction "VSYSTEM_J4-1") (pintype "passive"))
      (node (ref "U1") (pin "J4-2") (pinfunction "VSYSTEM_J4-2") (pintype "passive"))
      (node (ref "U2") (pin "19") (pinfunction "VccB_19") (pintype "passive"))
      (node (ref "U3") (pin "19") (pinfunction "VccB_19") (pintype "passive"))
      (node (ref "U5") (pin "1") (pinfunction "VIN_1") (pintype "power_in"))
      (node (ref "U5") (pin "3") (pinfunction "EN_3") (pintype "input"))
      (node (ref "U6") (pin "3") (pinfunction "VCC_3") (pintype "passive"))
    )
    (net (code "59") (name "VBUS") (class "Default")
      (node (ref "C9") (pin "2") (pinfunction "2_2") (pintype "passive"))
      (node (ref "CONN4") (pin "1") (pinfunction "VBUS_1") (pintype "passive"))
      (node (ref "D1") (pin "2") (pinfunction "A2_2") (pintype "passive"))
      (node (ref "R10") (pin "1") (pinfunction "1_1") (pintype "passive"))
    )
    (net (code "60") (name "VCC_UNREG") (class "Default")
      (node (ref "CONN1") (pin "2") (pinfunction "2_2") (pintype "passive"))
      (node (ref "CONN2") (pin "2") (pinfunction "2_2") (pintype "passive"))
      (node (ref "CONN3") (pin "2") (pinfunction "2_2") (pintype "passive"))
      (node (ref "D1") (pin "1") (pinfunction "A1_1") (pintype "passive"))
      (node (ref "R3") (pin "1") (pinfunction "1_1") (pintype "passive"))
    )
    (net (code "61") (name "unconnected-(U1A-GPIO163_IR_CTS3-PadJ1-22)") (class "Default")
      (node (ref "U1") (pin "J1-22") (pinfunction "GPIO163_IR_CTS3_J1-22") (pintype "passive"))
    )
    (net (code "62") (name "unconnected-(U1A-GPIO170_HDQ_1WIRE-PadJ1-47)") (class "Default")
      (node (ref "U1") (pin "J1-47") (pinfunction "GPIO170_HDQ_1WIRE_J1-47") (pintype "passive"))
    )
    (net (code "63") (name "unconnected-(U1A-GPIO184_I2C3_SCL-PadJ1-13)") (class "Default")
      (node (ref "U1") (pin "J1-13") (pinfunction "GPIO184_I2C3_SCL_J1-13") (pintype "passive"))
    )
    (net (code "64") (name "unconnected-(U1D-GPIO31_WAKEUP-PadJ1-9)") (class "Default")
      (node (ref "U1") (pin "J1-9") (pinfunction "GPIO31_WAKEUP_J1-9") (pintype "passive"))
    )
    (net (code "65") (name "unconnected-(U1D-NRESPWRON-PadJ1-1)") (class "Default")
      (node (ref "U1") (pin "J1-1") (pinfunction "NRESPWRON_J1-1") (pintype "passive"))
    )
    (net (code "66") (name "unconnected-(U1D-POWERON-PadJ1-65)") (class "Default")
      (node (ref "U1") (pin "J1-65") (pinfunction "POWERON_J1-65") (pintype "passive"))
    )
    (net (code "67") (name "unconnected-(U1D-SYSEN-PadJ1-59)") (class "Default")
      (node (ref "U1") (pin "J1-59") (pinfunction "SYSEN_J1-59") (pintype "passive"))
    )
    (net (code "68") (name "unconnected-(U1E-GPIO13_MMC3_CMD-PadJ4-23)") (class "Default")
      (node (ref "U1") (pin "J4-23") (pinfunction "GPIO13_MMC3_CMD_J4-23") (pintype "passive"))
    )
    (net (code "69") (name "unconnected-(U1E-GPIO17_MMC3_D3-PadJ4-31)") (class "Default")
      (node (ref "U1") (pin "J4-31") (pinfunction "GPIO17_MMC3_D3_J4-31") (pintype "passive"))
    )
    (net (code "70") (name "unconnected-(U1E-GPIO19_MMC3_D1-PadJ4-36)") (class "Default")
      (node (ref "U1") (pin "J4-36") (pinfunction "GPIO19_MMC3_D1_J4-36") (pintype "passive"))
    )
    (net (code "71") (name "unconnected-(U1E-GPIO20_MMC3_D2-PadJ4-39)") (class "Default")
      (node (ref "U1") (pin "J4-39") (pinfunction "GPIO20_MMC3_D2_J4-39") (pintype "passive"))
    )
    (net (code "72") (name "unconnected-(U1E-GPIO22_MMC3_DAT6-PadJ4-37)") (class "Default")
      (node (ref "U1") (pin "J4-37") (pinfunction "GPIO22_MMC3_DAT6_J4-37") (pintype "passive"))
    )
    (net (code "73") (name "unconnected-(U1E-GPIO23_MMC3_DAT5-PadJ4-38)") (class "Default")
      (node (ref "U1") (pin "J4-38") (pinfunction "GPIO23_MMC3_DAT5_J4-38") (pintype "passive"))
    )
    (net (code "74") (name "unconnected-(U1E-GPIO168_USBH_CPEN-PadJ4-28)") (class "Default")
      (node (ref "U1") (pin "J4-28") (pinfunction "GPIO168_USBH_CPEN_J4-28") (pintype "passive"))
    )
    (net (code "75") (name "unconnected-(U1E-GPIO174_SPI1_CS0-PadJ4-27)") (class "Default")
      (node (ref "U1") (pin "J4-27") (pinfunction "GPIO174_SPI1_CS0_J4-27") (pintype "passive"))
    )
    (net (code "76") (name "unconnected-(U1E-USBH_DM-PadJ4-35)") (class "Default")
      (node (ref "U1") (pin "J4-35") (pinfunction "USBH_DM_J4-35") (pintype "passive"))
    )
    (net (code "77") (name "unconnected-(U1E-USBH_DP-PadJ4-34)") (class "Default")
      (node (ref "U1") (pin "J4-34") (pinfunction "USBH_DP_J4-34") (pintype "passive"))
    )
    (net (code "78") (name "unconnected-(U1E-USBH_VBUS-PadJ4-32)") (class "Default")
      (node (ref "U1") (pin "J4-32") (pinfunction "USBH_VBUS_J4-32") (pintype "passive"))
    )
    (net (code "79") (name "unconnected-(U2-A1-Pad1)") (class "Default")
      (node (ref "U2") (pin "1") (pinfunction "A1_1") (pintype "passive"))
    )
    (net (code "80") (name "unconnected-(U2-B1-Pad20)") (class "Default")
      (node (ref "U2") (pin "20") (pinfunction "B1_20") (pintype "passive"))
    )
    (net (code "81") (name "unconnected-(U3-A1-Pad1)") (class "Default")
      (node (ref "U3") (pin "1") (pinfunction "A1_1") (pintype "passive"))
    )
    (net (code "82") (name "unconnected-(U3-A6-Pad7)") (class "Default")
      (node (ref "U3") (pin "7") (pinfunction "A6_7") (pintype "passive"))
    )
    (net (code "83") (name "unconnected-(U3-A7-Pad8)") (class "Default")
      (node (ref "U3") (pin "8") (pinfunction "A7_8") (pintype "passive"))
    )
    (net (code "84") (name "unconnected-(U3-A8-Pad9)") (class "Default")
      (node (ref "U3") (pin "9") (pinfunction "A8_9") (pintype "passive"))
    )
    (net (code "85") (name "unconnected-(U3-B1-Pad20)") (class "Default")
      (node (ref "U3") (pin "20") (pinfunction "B1_20") (pintype "passive"))
    )
    (net (code "86") (name "unconnected-(U3-B6-Pad14)") (class "Default")
      (node (ref "U3") (pin "14") (pinfunction "B6_14") (pintype "passive"))
    )
    (net (code "87") (name "unconnected-(U3-B7-Pad13)") (class "Default")
      (node (ref "U3") (pin "13") (pinfunction "B7_13") (pintype "passive"))
    )
    (net (code "88") (name "unconnected-(U3-B8-Pad12)") (class "Default")
      (node (ref "U3") (pin "12") (pinfunction "B8_12") (pintype "passive"))
    )
  )
)
